# Converter_Voltage_to_Current.net
KiCad netlist of a schematic drawn in Altium Designer
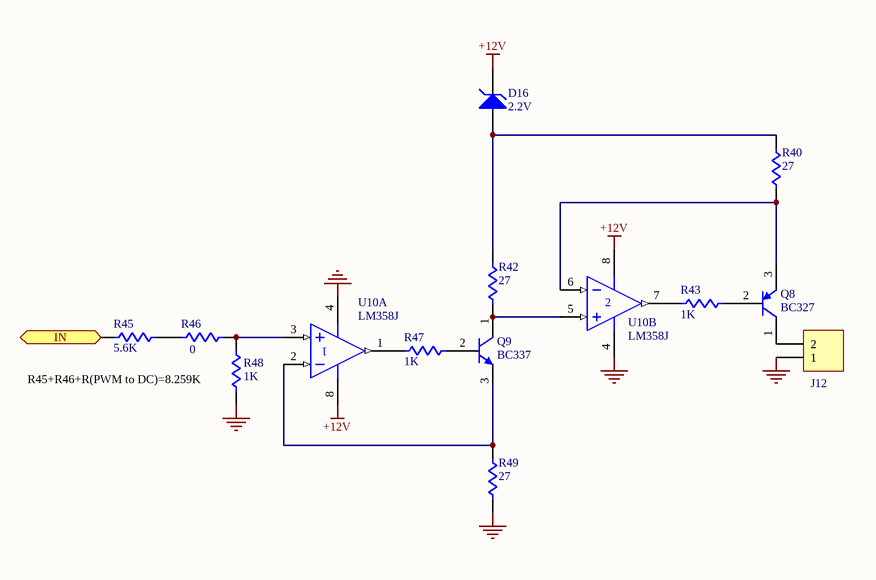
[diagram p0: Converter_Voltage to Current.SchDoc]

(export (version "E")
  (design (tool "Eeschema 10.0.6"))
  (components
    (comp (ref "D16")
      (value "2.2V")
      (footprint "DIODE-0.4")
      (description "Zener Diode")
      (fields
        (field (name "MANUFACTURER") "Generic Components")
        (field (name "Comment") "D Zener")
        (field (name "PUBLISHER") "Altium Limited")
      )
      (libsource (lib "Miscellaneous Devices") (part "D Zener"))
    )
    (comp (ref "J12")
      (value "Header 2")
      (footprint "Fonics_2PIN_1")
      (description "Header, 2-Pin")
      (fields (field (name "PUBLISHER") "Altium Limited"))
      (libsource (lib "Miscellaneous Connectors") (part "Header 2"))
    )
    (comp (ref "Q8")
      (value "PNP")
      (footprint "TO92C")
      (description "Silicon Bipolar Transistor")
      (fields (field (name "DEVICE") "BC327"))
      (libsource (lib "my Libraries") (part "PNP"))
    )
    (comp (ref "Q9")
      (value "BC337")
      (footprint "TO92C")
      (description "NPN Bipolar Transistor")
      (fields
        (field (name "MANUFACTURER") "Generic Components")
        (field (name "Comment") "NPN")
        (field (name "PUBLISHER") "Altium Limited")
      )
      (libsource (lib "Miscellaneous Devices") (part "NPN"))
    )
    (comp (ref "R40")
      (value "27")
      (footprint "AXIAL-0.4")
      (description "Resistor")
      (fields
        (field (name "MANUFACTURER") "Generic Components")
        (field (name "Comment") "Res1")
        (field (name "PUBLISHER") "Altium Limited")
      )
      (libsource (lib "Miscellaneous Devices") (part "Res1"))
    )
    (comp (ref "R42")
      (value "27")
      (footprint "AXIAL-0.4")
      (description "Resistor")
      (fields
        (field (name "MANUFACTURER") "Generic Components")
        (field (name "Comment") "Res1")
        (field (name "PUBLISHER") "Altium Limited")
      )
      (libsource (lib "Miscellaneous Devices") (part "Res1"))
    )
    (comp (ref "R43")
      (value "1K")
      (footprint "AXIAL-0.4")
      (description "Resistor")
      (fields
        (field (name "MANUFACTURER") "Generic Components")
        (field (name "Comment") "Res1")
        (field (name "PUBLISHER") "Altium Limited")
      )
      (libsource (lib "Miscellaneous Devices") (part "Res1"))
    )
    (comp (ref "R45")
      (value "5.6K")
      (footprint "AXIAL-0.4")
      (description "Resistor")
      (fields
        (field (name "MANUFACTURER") "Generic Components")
        (field (name "Comment") "Res1")
        (field (name "PUBLISHER") "Altium Limited")
      )
      (libsource (lib "Miscellaneous Devices") (part "Res1"))
    )
    (comp (ref "R46")
      (value "0")
      (footprint "AXIAL-0.4")
      (description "Resistor")
      (fields
        (field (name "MANUFACTURER") "Generic Components")
        (field (name "Comment") "Res1")
        (field (name "PUBLISHER") "Altium Limited")
      )
      (libsource (lib "Miscellaneous Devices") (part "Res1"))
    )
    (comp (ref "R47")
      (value "1K")
      (footprint "AXIAL-0.4")
      (description "Resistor")
      (fields
        (field (name "MANUFACTURER") "Generic Components")
        (field (name "Comment") "Res1")
        (field (name "PUBLISHER") "Altium Limited")
      )
      (libsource (lib "Miscellaneous Devices") (part "Res1"))
    )
    (comp (ref "R48")
      (value "1K")
      (footprint "AXIAL-0.4")
      (description "Resistor")
      (fields
        (field (name "MANUFACTURER") "Generic Components")
        (field (name "Comment") "Res1")
        (field (name "PUBLISHER") "Altium Limited")
      )
      (libsource (lib "Miscellaneous Devices") (part "Res1"))
    )
    (comp (ref "R49")
      (value "27")
      (footprint "AXIAL-0.4")
      (description "Resistor")
      (fields
        (field (name "MANUFACTURER") "Generic Components")
        (field (name "Comment") "Res1")
        (field (name "PUBLISHER") "Altium Limited")
      )
      (libsource (lib "Miscellaneous Devices") (part "Res1"))
    )
    (comp (ref "U10")
      (value "LM358J")
      (footprint "693-02")
      (description "Dual Low-Power Operational Amplifier")
      (fields (field (name "PUBLISHER") "Altium Limited"))
      (libsource (lib "Motorola Amplifier Operational Amplifier") (part "LM358J"))
    )
  )
  (nets
    (net (code "1") (name "+12V") (class "Default")
      (node (ref "D16") (pin "2") (pinfunction "K_2") (pintype "passive"))
      (node (ref "U10") (pin "8") (pinfunction "V+_8") (pintype "power_in"))
    )
    (net (code "2") (name "/IN") (class "Default")
      (node (ref "R45") (pin "1") (pinfunction "1_1") (pintype "passive"))
    )
    (net (code "3") (name "GND") (class "Default")
      (node (ref "J12") (pin "1") (pinfunction "1_1") (pintype "passive"))
      (node (ref "R48") (pin "2") (pinfunction "2_2") (pintype "passive"))
      (node (ref "R49") (pin "1") (pinfunction "1_1") (pintype "passive"))
      (node (ref "U10") (pin "4") (pinfunction "V-_4") (pintype "power_in"))
    )
    (net (code "4") (name "Net-(D16-A)") (class "Default")
      (node (ref "D16") (pin "1") (pinfunction "A_1") (pintype "passive"))
      (node (ref "R40") (pin "2") (pinfunction "2_2") (pintype "passive"))
      (node (ref "R42") (pin "2") (pinfunction "2_2") (pintype "passive"))
    )
    (net (code "5") (name "Net-(Q8-B)") (class "Default")
      (node (ref "Q8") (pin "2") (pinfunction "B_2") (pintype "passive"))
      (node (ref "R43") (pin "2") (pinfunction "2_2") (pintype "passive"))
    )
    (net (code "6") (name "Net-(Q8-C)") (class "Default")
      (node (ref "J12") (pin "2") (pinfunction "2_2") (pintype "passive"))
      (node (ref "Q8") (pin "1") (pinfunction "C_1") (pintype "passive"))
    )
    (net (code "7") (name "Net-(Q8-E)") (class "Default")
      (node (ref "Q8") (pin "3") (pinfunction "E_3") (pintype "passive"))
      (node (ref "R40") (pin "1") (pinfunction "1_1") (pintype "passive"))
      (node (ref "U10") (pin "6") (pinfunction "IN-_6") (pintype "input"))
    )
    (net (code "8") (name "Net-(Q9-B)") (class "Default")
      (node (ref "Q9") (pin "2") (pinfunction "B_2") (pintype "passive"))
      (node (ref "R47") (pin "2") (pinfunction "2_2") (pintype "passive"))
    )
    (net (code "9") (name "Net-(Q9-C)") (class "Default")
      (node (ref "Q9") (pin "1") (pinfunction "C_1") (pintype "passive"))
      (node (ref "R42") (pin "1") (pinfunction "1_1") (pintype "passive"))
      (node (ref "U10") (pin "5") (pinfunction "IN+_5") (pintype "input"))
    )
    (net (code "10") (name "Net-(Q9-E)") (class "Default")
      (node (ref "Q9") (pin "3") (pinfunction "E_3") (pintype "passive"))
      (node (ref "R49") (pin "2") (pinfunction "2_2") (pintype "passive"))
      (node (ref "U10") (pin "2") (pinfunction "IN-_2") (pintype "input"))
    )
    (net (code "11") (name "Net-(R45-Pad2)") (class "Default")
      (node (ref "R45") (pin "2") (pinfunction "2_2") (pintype "passive"))
      (node (ref "R46") (pin "1") (pinfunction "1_1") (pintype "passive"))
    )
    (net (code "12") (name "Net-(U10A-IN+)") (class "Default")
      (node (ref "R46") (pin "2") (pinfunction "2_2") (pintype "passive"))
      (node (ref "R48") (pin "1") (pinfunction "1_1") (pintype "passive"))
      (node (ref "U10") (pin "3") (pinfunction "IN+_3") (pintype "input"))
    )
    (net (code "13") (name "Net-(U10A-OUT)") (class "Default")
      (node (ref "R47") (pin "1") (pinfunction "1_1") (pintype "passive"))
      (node (ref "U10") (pin "1") (pinfunction "OUT_1") (pintype "output"))
    )
    (net (code "14") (name "Net-(U10B-OUT)") (class "Default")
      (node (ref "R43") (pin "1") (pinfunction "1_1") (pintype "passive"))
      (node (ref "U10") (pin "7") (pinfunction "OUT_7") (pintype "output"))
    )
  )
)
